# IMU.net
KiCad netlist of a schematic drawn in Altium Designer
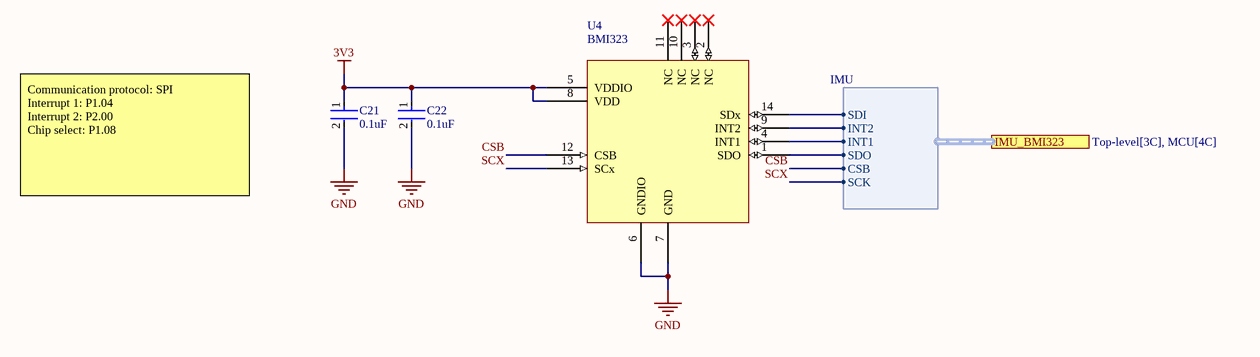
[diagram p0: IMU.SchDoc]

(export (version "E")
  (design (tool "Eeschema 10.0.6"))
  (components
    (comp (ref "C21")
      (value "0.1uF")
      (footprint "FP-GRM033-0_03-MFG")
      (description "Chip Multilayer Ceramic Capacitors for General Purpose, 0201, 0.10uF, X7S, 22%, 10%, 16V")
      (fields (field (name "TOLERANCE") "10%"))
      (libsource (lib "Altium Content Vault") (part "b4654b650e69147ec39a6b967a45e02"))
    )
    (comp (ref "C22")
      (value "0.1uF")
      (footprint "FP-GRM033-0_03-MFG")
      (description "Chip Multilayer Ceramic Capacitors for General Purpose, 0201, 0.10uF, X7S, 22%, 10%, 16V")
      (fields (field (name "TOLERANCE") "10%"))
      (libsource (lib "Altium Content Vault") (part "b4654b650e69147ec39a6b967a45e02"))
    )
    (comp (ref "U4") (value "BMI323") (footprint "BMI323") (libsource (lib "MyCustomLib") (part "BMI323")))
  )
  (nets
    (net (code "2") (name "/CSB") (class "Default")
      (node (ref "U4") (pin "12") (pinfunction "CSB_12") (pintype "input"))
    )
    (net (code "3") (name "/INT1") (class "Default")
      (node (ref "U4") (pin "4") (pinfunction "INT1_4") (pintype "bidirectional"))
    )
    (net (code "4") (name "/INT2") (class "Default")
      (node (ref "U4") (pin "9") (pinfunction "INT2_9") (pintype "bidirectional"))
    )
    (net (code "5") (name "/SCX") (class "Default")
      (node (ref "U4") (pin "13") (pinfunction "SCx_13") (pintype "input"))
    )
    (net (code "6") (name "/SDI") (class "Default")
      (node (ref "U4") (pin "14") (pinfunction "SDx_14") (pintype "bidirectional"))
    )
    (net (code "7") (name "/SDO") (class "Default")
      (node (ref "U4") (pin "1") (pinfunction "SDO_1") (pintype "bidirectional"))
    )
    (net (code "9") (name "3V3") (class "Default")
      (node (ref "C21") (pin "1") (pinfunction "1_1") (pintype "passive"))
      (node (ref "C22") (pin "1") (pinfunction "1_1") (pintype "passive"))
      (node (ref "U4") (pin "5") (pinfunction "VDDIO_5") (pintype "power_in"))
      (node (ref "U4") (pin "8") (pinfunction "VDD_8") (pintype "power_in"))
    )
    (net (code "10") (name "GND") (class "Default")
      (node (ref "C21") (pin "2") (pinfunction "2_2") (pintype "passive"))
      (node (ref "C22") (pin "2") (pinfunction "2_2") (pintype "passive"))
      (node (ref "U4") (pin "6") (pinfunction "GNDIO_6") (pintype "power_in"))
      (node (ref "U4") (pin "7") (pinfunction "GND_7") (pintype "power_in"))
    )
    (net (code "11") (name "unconnected-(U4-NC-Pad2)") (class "Default")
      (node (ref "U4") (pin "2") (pinfunction "NC_2") (pintype "bidirectional+no_connect"))
    )
    (net (code "12") (name "unconnected-(U4-NC-Pad3)") (class "Default")
      (node (ref "U4") (pin "3") (pinfunction "NC_3") (pintype "bidirectional+no_connect"))
    )
    (net (code "13") (name "unconnected-(U4-NC-Pad10)") (class "Default")
      (node (ref "U4") (pin "10") (pinfunction "NC_10") (pintype "passive+no_connect"))
    )
    (net (code "14") (name "unconnected-(U4-NC-Pad11)") (class "Default")
      (node (ref "U4") (pin "11") (pinfunction "NC_11") (pintype "passive+no_connect"))
    )
  )
)
